# TSOC_PSoC4L.net
KiCad netlist of a schematic drawn in EAGLE
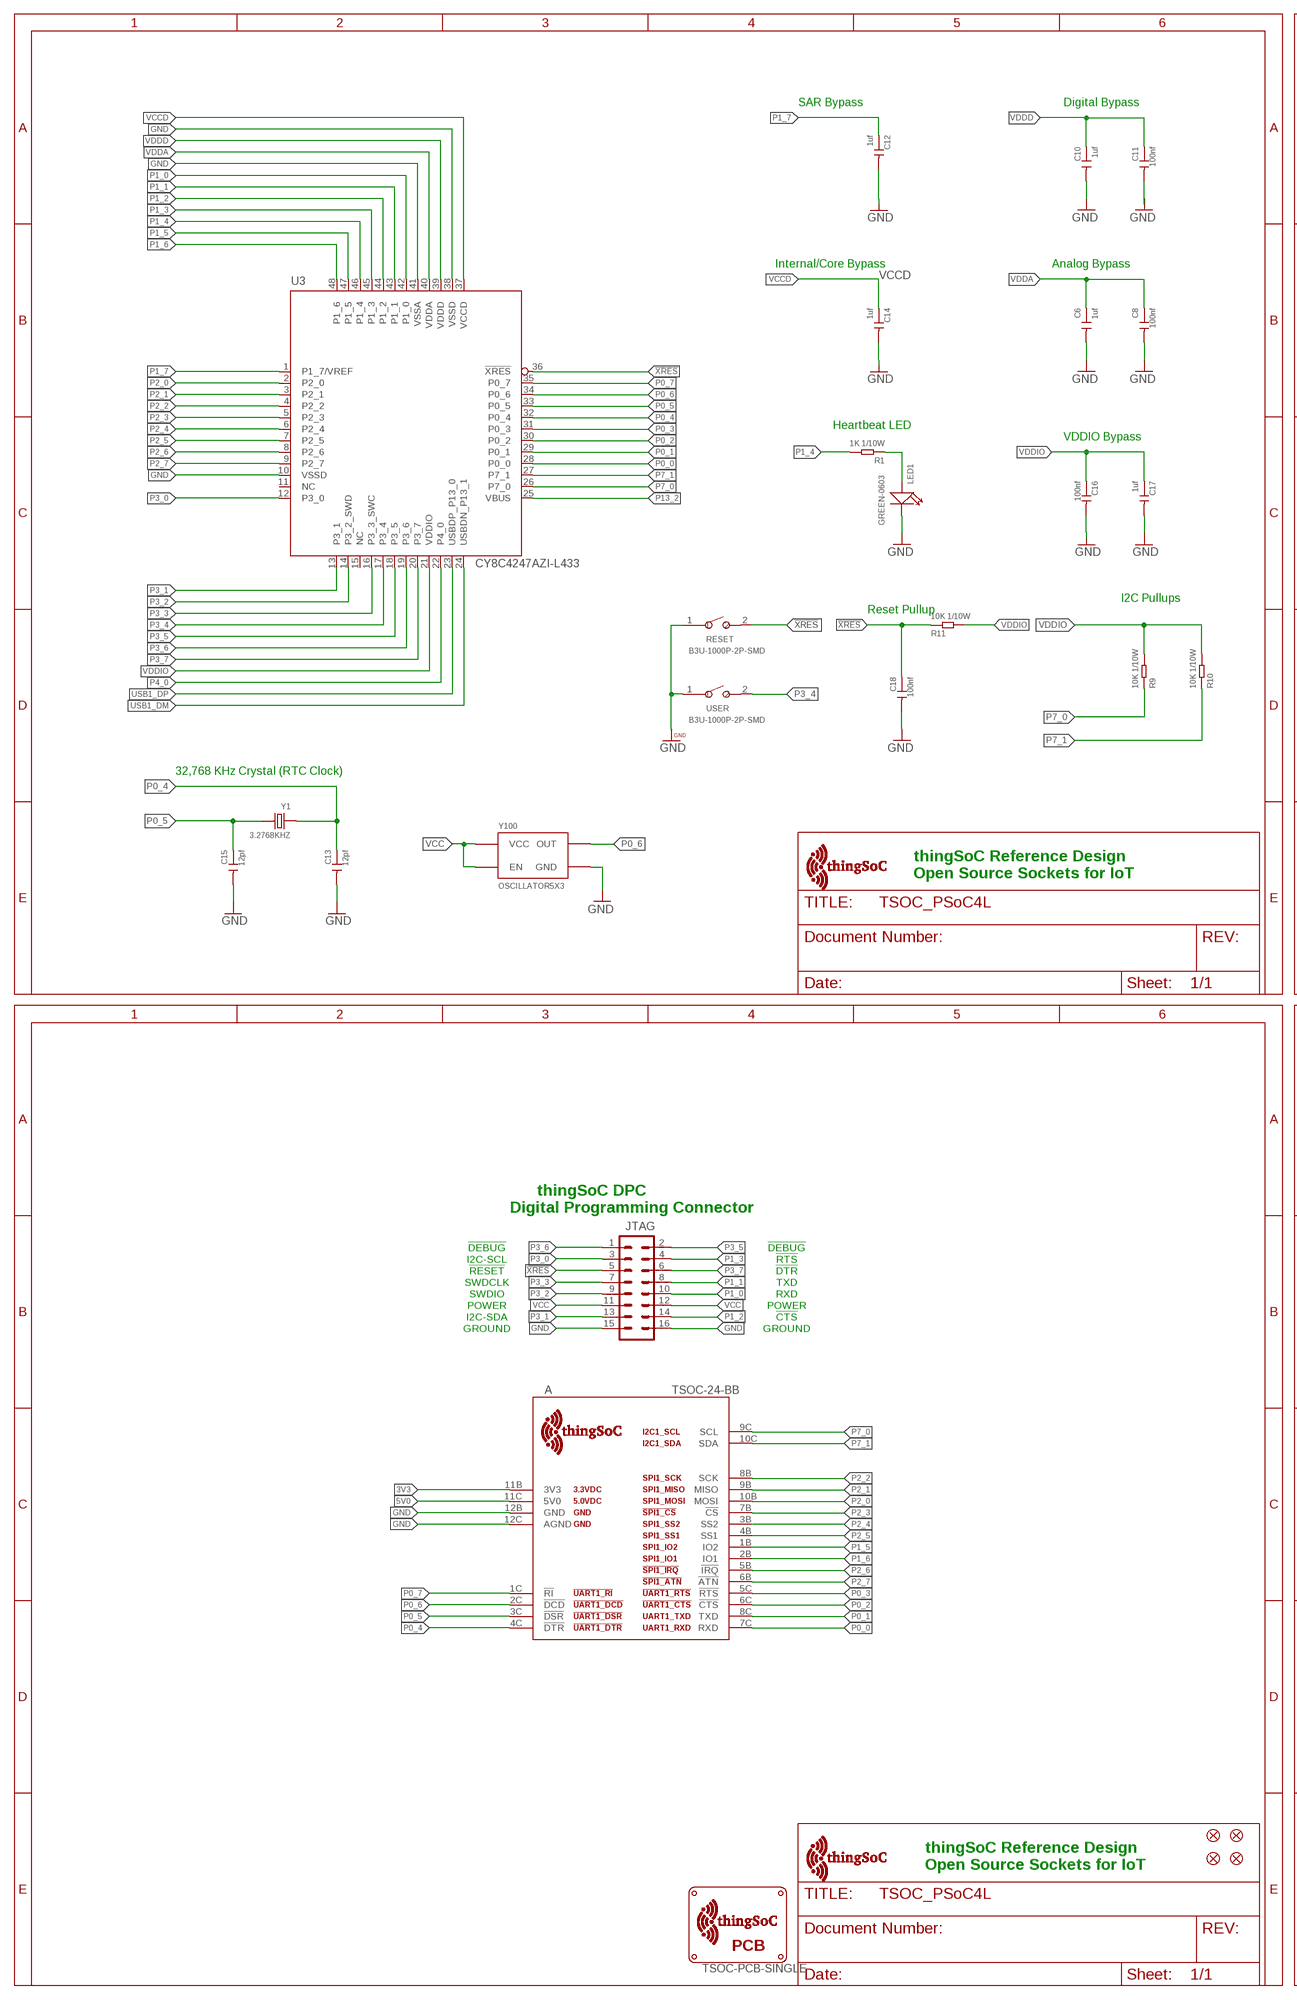
[diagram p0: schematic, sheet 1, part 1 of 2]
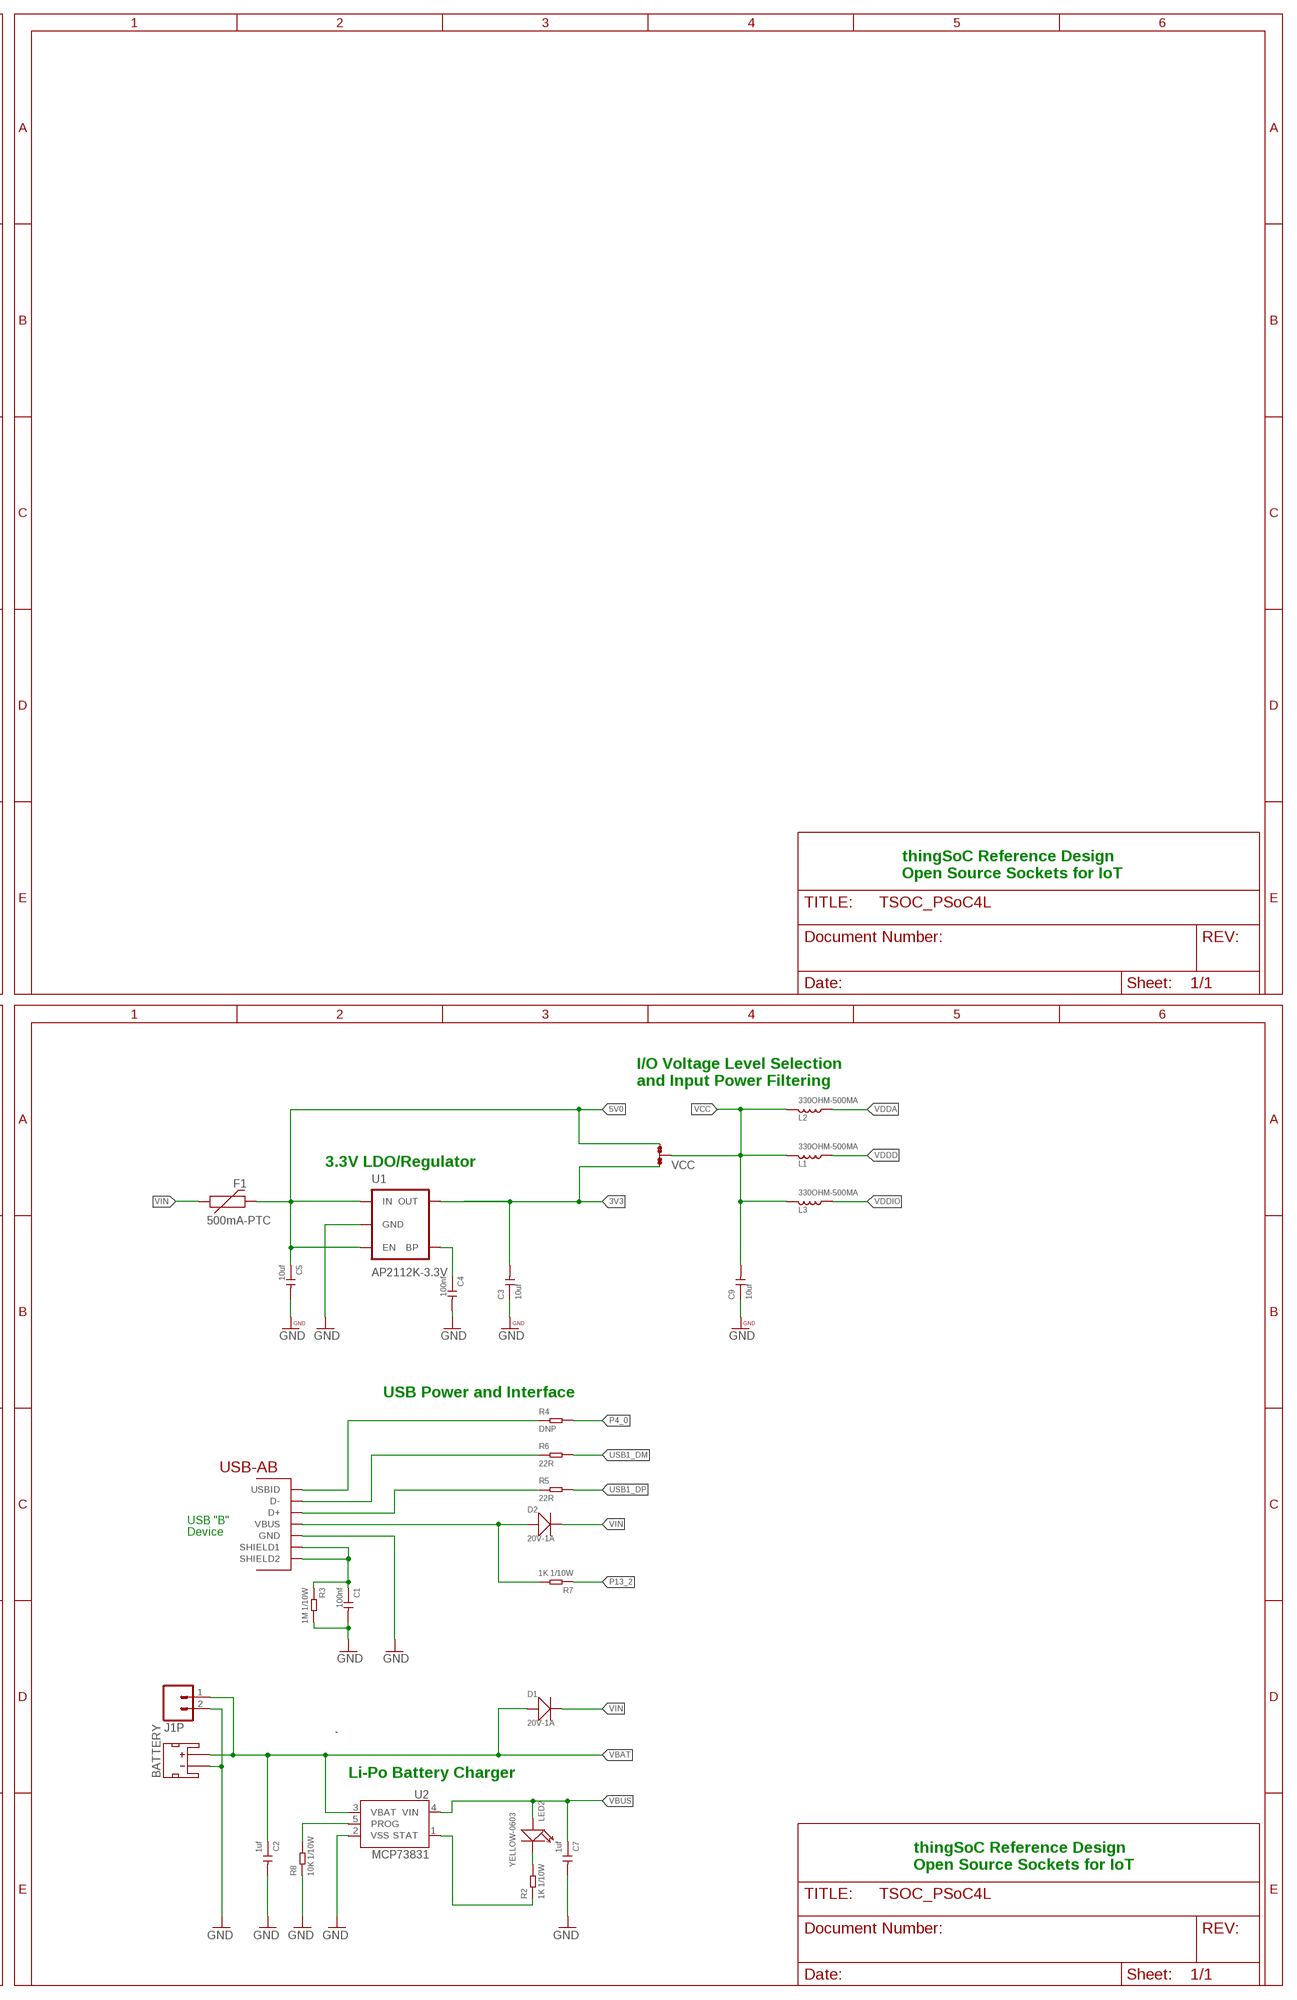
[diagram p1: schematic, sheet 1, part 2 of 2]

(export (version "E")
  (design (tool "Eeschema 10.0.6"))
  (components
    (comp (ref "A")
      (value "TSOC-24-BB")
      (footprint "eagle-import:TSOC-BB-S24")
      (libsource (lib "eagle-import") (part "TSOC-24-BB"))
    )
    (comp (ref "BATTERY")
      (value "JST_2MM_MALE")
      (footprint "eagle-import:JST-2-SMD")
      (libsource (lib "eagle-import") (part "JST_2MM_MALE"))
    )
    (comp (ref "C1")
      (value "100nf")
      (footprint "eagle-import:C0603")
      (fields (field (name "MPN") "CC0603KRX7R9BB104"))
      (libsource (lib "eagle-import") (part "CERAMIC-100NF-50V-10%-X7R(0603)"))
    )
    (comp (ref "C2")
      (value "1uf")
      (footprint "eagle-import:C0603")
      (fields (field (name "MPN") "CC0603KRX7R8BB105"))
      (libsource (lib "eagle-import") (part "CERAMIC-1UF-25V-10%-X7R(0603)"))
    )
    (comp (ref "C3")
      (value "10uf")
      (footprint "eagle-import:C0603")
      (fields (field (name "MPN") "CC0603KRX5R6BB106"))
      (libsource (lib "eagle-import") (part "CERAMIC-10UF-10V-10%-X5R(0603)"))
    )
    (comp (ref "C4")
      (value "100nf")
      (footprint "eagle-import:C0603")
      (fields (field (name "MPN") "CC0603KRX7R9BB104"))
      (libsource (lib "eagle-import") (part "CERAMIC-100NF-50V-10%-X7R(0603)"))
    )
    (comp (ref "C5")
      (value "10uf")
      (footprint "eagle-import:C0603")
      (fields (field (name "MPN") "CC0603KRX5R6BB106"))
      (libsource (lib "eagle-import") (part "CERAMIC-10UF-10V-10%-X5R(0603)"))
    )
    (comp (ref "C6")
      (value "1uf")
      (footprint "eagle-import:C0603")
      (fields (field (name "MPN") "CC0603KRX7R8BB105"))
      (libsource (lib "eagle-import") (part "CERAMIC-1UF-25V-10%-X7R(0603)"))
    )
    (comp (ref "C7")
      (value "1uf")
      (footprint "eagle-import:C0603")
      (fields (field (name "MPN") "CC0603KRX7R8BB105"))
      (libsource (lib "eagle-import") (part "CERAMIC-1UF-25V-10%-X7R(0603)"))
    )
    (comp (ref "C8")
      (value "100nf")
      (footprint "eagle-import:C0603")
      (fields (field (name "MPN") "CC0603KRX7R9BB104"))
      (libsource (lib "eagle-import") (part "CERAMIC-100NF-50V-10%-X7R(0603)"))
    )
    (comp (ref "C9")
      (value "10uf")
      (footprint "eagle-import:C0603")
      (fields (field (name "MPN") "CC0603KRX5R6BB106"))
      (libsource (lib "eagle-import") (part "CERAMIC-10UF-10V-10%-X5R(0603)"))
    )
    (comp (ref "C10")
      (value "1uf")
      (footprint "eagle-import:C0603")
      (fields (field (name "MPN") "CC0603KRX7R8BB105"))
      (libsource (lib "eagle-import") (part "CERAMIC-1UF-25V-10%-X7R(0603)"))
    )
    (comp (ref "C11")
      (value "100nf")
      (footprint "eagle-import:C0603")
      (fields (field (name "MPN") "CC0603KRX7R9BB104"))
      (libsource (lib "eagle-import") (part "CERAMIC-100NF-50V-10%-X7R(0603)"))
    )
    (comp (ref "C12")
      (value "1uf")
      (footprint "eagle-import:C0603")
      (fields (field (name "MPN") "CC0603KRX7R8BB105"))
      (libsource (lib "eagle-import") (part "CERAMIC-1UF-25V-10%-X7R(0603)"))
    )
    (comp (ref "C13")
      (value "12pf")
      (footprint "eagle-import:C0603")
      (fields (field (name "MPN") "CC0603JRNPO9BN120"))
      (libsource (lib "eagle-import") (part "CERAMIC-12PF-50V-5%-NPO(0603)"))
    )
    (comp (ref "C14")
      (value "1uf")
      (footprint "eagle-import:C0603")
      (fields (field (name "MPN") "CC0603KRX7R8BB105"))
      (libsource (lib "eagle-import") (part "CERAMIC-1UF-25V-10%-X7R(0603)"))
    )
    (comp (ref "C15")
      (value "12pf")
      (footprint "eagle-import:C0603")
      (fields (field (name "MPN") "CC0603JRNPO9BN120"))
      (libsource (lib "eagle-import") (part "CERAMIC-12PF-50V-5%-NPO(0603)"))
    )
    (comp (ref "C16")
      (value "100nf")
      (footprint "eagle-import:C0603")
      (fields (field (name "MPN") "CC0603KRX7R9BB104"))
      (libsource (lib "eagle-import") (part "CERAMIC-100NF-50V-10%-X7R(0603)"))
    )
    (comp (ref "C17")
      (value "1uf")
      (footprint "eagle-import:C0603")
      (fields (field (name "MPN") "CC0603KRX7R8BB105"))
      (libsource (lib "eagle-import") (part "CERAMIC-1UF-25V-10%-X7R(0603)"))
    )
    (comp (ref "C18")
      (value "100nf")
      (footprint "eagle-import:C0603")
      (fields (field (name "MPN") "CC0603KRX7R9BB104"))
      (libsource (lib "eagle-import") (part "CERAMIC-100NF-50V-10%-X7R(0603)"))
    )
    (comp (ref "D1")
      (value "20V-1A")
      (footprint "eagle-import:SOD-123")
      (fields (field (name "MPN") "B5819W"))
      (libsource (lib "eagle-import") (part "SMD-DIODE-SCHOTTKY-20V-1A(SOD-123)"))
    )
    (comp (ref "D2")
      (value "20V-1A")
      (footprint "eagle-import:SOD-123")
      (fields (field (name "MPN") "B5819W"))
      (libsource (lib "eagle-import") (part "SMD-DIODE-SCHOTTKY-20V-1A(SOD-123)"))
    )
    (comp (ref "F1")
      (value "500mA-PTC")
      (footprint "eagle-import:PTC-1206")
      (libsource (lib "eagle-import") (part "PTCSMD"))
    )
    (comp (ref "FID1")
      (value "FIDUCIALUFIDUCIAL")
      (footprint "eagle-import:MICRO-FIDUCIAL")
      (libsource (lib "eagle-import") (part "FIDUCIALUFIDUCIAL"))
    )
    (comp (ref "FID2")
      (value "FIDUCIALUFIDUCIAL")
      (footprint "eagle-import:MICRO-FIDUCIAL")
      (libsource (lib "eagle-import") (part "FIDUCIALUFIDUCIAL"))
    )
    (comp (ref "FID3")
      (value "FIDUCIALUFIDUCIAL")
      (footprint "eagle-import:MICRO-FIDUCIAL")
      (libsource (lib "eagle-import") (part "FIDUCIALUFIDUCIAL"))
    )
    (comp (ref "FID4")
      (value "FIDUCIALUFIDUCIAL")
      (footprint "eagle-import:MICRO-FIDUCIAL")
      (libsource (lib "eagle-import") (part "FIDUCIALUFIDUCIAL"))
    )
    (comp (ref "J1P")
      (value "M02-JST-2-PTH-NO_SILK")
      (footprint "eagle-import:JST-2-PTH-NS")
      (libsource (lib "eagle-import") (part "M02-JST-2-PTH-NO_SILK"))
    )
    (comp (ref "JTAG")
      (value "M08X2")
      (footprint "eagle-import:2X8")
      (libsource (lib "eagle-import") (part "M08X2"))
    )
    (comp (ref "L1")
      (value "330OHM-500MA")
      (footprint "eagle-import:L0603")
      (fields (field (name "MPN") "BLM18AG121SN1D"))
      (libsource (lib "eagle-import") (part "SMD-FERRITE-CHIP-120-OHM-500MA(0603)"))
    )
    (comp (ref "L2")
      (value "330OHM-500MA")
      (footprint "eagle-import:L0603")
      (fields (field (name "MPN") "BLM18AG121SN1D"))
      (libsource (lib "eagle-import") (part "SMD-FERRITE-CHIP-120-OHM-500MA(0603)"))
    )
    (comp (ref "L3")
      (value "330OHM-500MA")
      (footprint "eagle-import:L0603")
      (fields (field (name "MPN") "BLM18AG121SN1D"))
      (libsource (lib "eagle-import") (part "SMD-FERRITE-CHIP-120-OHM-500MA(0603)"))
    )
    (comp (ref "LED1")
      (value "GREEN-0603")
      (footprint "eagle-import:LED-0603")
      (fields (field (name "MPN") "19-217-G7C-AN1P2-3T"))
      (libsource (lib "eagle-import") (part "SMD-LED-CLEAR-GREEN(0603)"))
    )
    (comp (ref "LED2")
      (value "YELLOW-0603")
      (footprint "eagle-import:LED-0603")
      (fields (field (name "MPN") "19-217-Y5C-AM1N1VY-3T"))
      (libsource (lib "eagle-import") (part "SMD-LED-CLEAR-YELLOW(0603)"))
    )
    (comp (ref "R1")
      (value "1K 1/10W")
      (footprint "eagle-import:R0603")
      (fields (field (name "MPN") "RC0603JR-071KL"))
      (libsource (lib "eagle-import") (part "SMD-RES-1K-5%-1/10W(0603)"))
    )
    (comp (ref "R2")
      (value "1K 1/10W")
      (footprint "eagle-import:R0603")
      (fields (field (name "MPN") "RC0603JR-071KL"))
      (libsource (lib "eagle-import") (part "SMD-RES-1K-5%-1/10W(0603)"))
    )
    (comp (ref "R3")
      (value "1M 1/10W")
      (footprint "eagle-import:R0603")
      (fields (field (name "MPN") "RC0603JR-071ML"))
      (libsource (lib "eagle-import") (part "SMD-RES-1M-5%-1/10W(0603)"))
    )
    (comp (ref "R4")
      (value "DNP")
      (footprint "eagle-import:R0603")
      (fields (field (name "MPN") "RC0603JR-0722RL"))
      (libsource (lib "eagle-import") (part "SMD-RES-22R-5%-1/10W(0603)"))
    )
    (comp (ref "R5")
      (value "22R")
      (footprint "eagle-import:R0603")
      (fields (field (name "MPN") "RC0603JR-0722RL"))
      (libsource (lib "eagle-import") (part "SMD-RES-22R-5%-1/10W(0603)"))
    )
    (comp (ref "R6")
      (value "22R")
      (footprint "eagle-import:R0603")
      (fields (field (name "MPN") "RC0603JR-0722RL"))
      (libsource (lib "eagle-import") (part "SMD-RES-22R-5%-1/10W(0603)"))
    )
    (comp (ref "R7")
      (value "1K 1/10W")
      (footprint "eagle-import:R0603")
      (fields (field (name "MPN") "RC0603JR-071KL"))
      (libsource (lib "eagle-import") (part "SMD-RES-1K-5%-1/10W(0603)"))
    )
    (comp (ref "R8")
      (value "10K 1/10W")
      (footprint "eagle-import:R0603")
      (fields (field (name "MPN") "RC0603JR-0710KL"))
      (libsource (lib "eagle-import") (part "SMD-RES-10K-5%-1/10W(0603)"))
    )
    (comp (ref "R9")
      (value "10K 1/10W")
      (footprint "eagle-import:R0603")
      (fields (field (name "MPN") "RC0603JR-0710KL"))
      (libsource (lib "eagle-import") (part "SMD-RES-10K-5%-1/10W(0603)"))
    )
    (comp (ref "R10")
      (value "10K 1/10W")
      (footprint "eagle-import:R0603")
      (fields (field (name "MPN") "RC0603JR-0710KL"))
      (libsource (lib "eagle-import") (part "SMD-RES-10K-5%-1/10W(0603)"))
    )
    (comp (ref "R11")
      (value "10K 1/10W")
      (footprint "eagle-import:R0603")
      (fields (field (name "MPN") "RC0603JR-0710KL"))
      (libsource (lib "eagle-import") (part "SMD-RES-10K-5%-1/10W(0603)"))
    )
    (comp (ref "RESET")
      (value "B3U-1000P-2P-SMD")
      (footprint "eagle-import:SW2-2.6-3.0X2.5X1.2+0.4MM")
      (libsource (lib "eagle-import") (part "SMD-BUTTON(2P-3.0X2.5X1.2+0.4MM)-B3U-1000P-2P-SMD"))
    )
    (comp (ref "U$1")
      (value "TSOC-PCB-SINGLE")
      (footprint "eagle-import:TSOC-BB-BRD-DIM")
      (libsource (lib "eagle-import") (part "TSOC-PCB-SINGLE"))
    )
    (comp (ref "U$100")
      (value "TSOC-LOGO-LRG")
      (footprint "eagle-import:TSOC-LOGO-LRG")
      (libsource (lib "eagle-import") (part "TSOC-LOGO-LRG"))
    )
    (comp (ref "U$101")
      (value "TSOC-LOGO-SMALL")
      (footprint "eagle-import:TSOC-LOGO-SML")
      (libsource (lib "eagle-import") (part "TSOC-LOGO-SMALL"))
    )
    (comp (ref "U1")
      (value "AP2112K-3.3V")
      (footprint "eagle-import:SOT23-5")
      (libsource (lib "eagle-import") (part "V_REG_LDOSMD"))
    )
    (comp (ref "U2")
      (value "MCP73831")
      (footprint "eagle-import:SOT23-5")
      (libsource (lib "eagle-import") (part "MCP73831"))
    )
    (comp (ref "U3")
      (value "CY8C4247AZI-L433")
      (footprint "eagle-import:TQFP-7X7-48")
      (libsource (lib "eagle-import") (part "CY8C4247AZI-L433"))
    )
    (comp (ref "USB")
      (value "USB_AB")
      (footprint "eagle-import:USB-AB-MICRO-SMD")
      (libsource (lib "eagle-import") (part "USB_AB"))
    )
    (comp (ref "USER")
      (value "B3U-1000P-2P-SMD")
      (footprint "eagle-import:SW2-2.6-3.0X2.5X1.2+0.4MM")
      (libsource (lib "eagle-import") (part "SMD-BUTTON(2P-3.0X2.5X1.2+0.4MM)-B3U-1000P-2P-SMD"))
    )
    (comp (ref "VCC")
      (value "JMP-3-1_2")
      (footprint "eagle-import:JMP-3-1_2")
      (libsource (lib "eagle-import") (part "JMP-3-1_2"))
    )
    (comp (ref "Y1")
      (value "3.2768KHZ")
      (footprint "eagle-import:X2-SMD-L2.0X1.2X0.55MM")
      (fields (field (name "MPN") "FC-12M"))
      (libsource (lib "eagle-import") (part "SMD-CRYSTAL-32.768KHZ-12.5PF-20PPM-90K(2P-L2.0X1.2MM)"))
    )
    (comp (ref "Y100")
      (value "OSCILLATOR5X3")
      (footprint "eagle-import:CRYSTAL-SMD-5X3")
      (libsource (lib "eagle-import") (part "OSCILLATOR5X3"))
    )
  )
  (nets
    (net (code "1") (name "/~{XRES}") (class "Default")
      (node (ref "C18") (pin "1") (pinfunction "1_1") (pintype "passive"))
      (node (ref "JTAG") (pin "5") (pinfunction "5_5") (pintype "passive"))
      (node (ref "R11") (pin "1") (pinfunction "1_1") (pintype "passive"))
      (node (ref "RESET") (pin "2") (pinfunction "2_2") (pintype "bidirectional"))
      (node (ref "U3") (pin "36") (pinfunction "~{XRES}_36") (pintype "bidirectional"))
    )
    (net (code "2") (name "3V3") (class "Default")
      (node (ref "A") (pin "11B") (pinfunction "3V3_11B") (pintype "bidirectional"))
      (node (ref "C3") (pin "2") (pinfunction "2_2") (pintype "passive"))
      (node (ref "U1") (pin "5") (pinfunction "OUT_5") (pintype "passive"))
      (node (ref "VCC") (pin "1") (pinfunction "1_1") (pintype "passive"))
    )
    (net (code "3") (name "5V0") (class "Default")
      (node (ref "A") (pin "11C") (pinfunction "5V0_11C") (pintype "bidirectional"))
      (node (ref "C5") (pin "1") (pinfunction "1_1") (pintype "passive"))
      (node (ref "F1") (pin "2") (pinfunction "2_2") (pintype "bidirectional"))
      (node (ref "U1") (pin "1") (pinfunction "IN_1") (pintype "input"))
      (node (ref "U1") (pin "3") (pinfunction "EN_3") (pintype "input"))
      (node (ref "VCC") (pin "3") (pinfunction "3_3") (pintype "passive"))
    )
    (net (code "4") (name "GND") (class "Default")
      (node (ref "A") (pin "12B") (pinfunction "GND_12B") (pintype "bidirectional"))
      (node (ref "A") (pin "12C") (pinfunction "AGND_12C") (pintype "bidirectional"))
      (node (ref "BATTERY") (pin "1") (pinfunction "-_1") (pintype "bidirectional"))
      (node (ref "C1") (pin "2") (pinfunction "2_2") (pintype "passive"))
      (node (ref "C10") (pin "2") (pinfunction "2_2") (pintype "passive"))
      (node (ref "C11") (pin "2") (pinfunction "2_2") (pintype "passive"))
      (node (ref "C12") (pin "2") (pinfunction "2_2") (pintype "passive"))
      (node (ref "C13") (pin "2") (pinfunction "2_2") (pintype "passive"))
      (node (ref "C14") (pin "2") (pinfunction "2_2") (pintype "passive"))
      (node (ref "C15") (pin "2") (pinfunction "2_2") (pintype "passive"))
      (node (ref "C16") (pin "2") (pinfunction "2_2") (pintype "passive"))
      (node (ref "C17") (pin "2") (pinfunction "2_2") (pintype "passive"))
      (node (ref "C18") (pin "2") (pinfunction "2_2") (pintype "passive"))
      (node (ref "C2") (pin "2") (pinfunction "2_2") (pintype "passive"))
      (node (ref "C3") (pin "1") (pinfunction "1_1") (pintype "passive"))
      (node (ref "C4") (pin "2") (pinfunction "2_2") (pintype "passive"))
      (node (ref "C5") (pin "2") (pinfunction "2_2") (pintype "passive"))
      (node (ref "C6") (pin "2") (pinfunction "2_2") (pintype "passive"))
      (node (ref "C7") (pin "2") (pinfunction "2_2") (pintype "passive"))
      (node (ref "C8") (pin "2") (pinfunction "2_2") (pintype "passive"))
      (node (ref "C9") (pin "1") (pinfunction "1_1") (pintype "passive"))
      (node (ref "J1P") (pin "2") (pinfunction "2_2") (pintype "passive"))
      (node (ref "JTAG") (pin "15") (pinfunction "15_15") (pintype "passive"))
      (node (ref "JTAG") (pin "16") (pinfunction "16_16") (pintype "passive"))
      (node (ref "LED1") (pin "-") (pinfunction "-_-") (pintype "passive"))
      (node (ref "R3") (pin "2") (pinfunction "2_2") (pintype "passive"))
      (node (ref "R8") (pin "1") (pinfunction "1_1") (pintype "passive"))
      (node (ref "RESET") (pin "1") (pinfunction "1_1") (pintype "bidirectional"))
      (node (ref "U1") (pin "2") (pinfunction "GND_2") (pintype "input"))
      (node (ref "U2") (pin "2") (pinfunction "VSS_2") (pintype "power_in"))
      (node (ref "U3") (pin "10") (pinfunction "VSSD_10") (pintype "bidirectional"))
      (node (ref "U3") (pin "38") (pinfunction "VSSD_38") (pintype "bidirectional"))
      (node (ref "U3") (pin "41") (pinfunction "VSSA_41") (pintype "bidirectional"))
      (node (ref "USB") (pin "GND") (pinfunction "GND_GND") (pintype "bidirectional"))
      (node (ref "USER") (pin "1") (pinfunction "1_1") (pintype "bidirectional"))
      (node (ref "Y100") (pin "2") (pinfunction "GND_2") (pintype "bidirectional"))
    )
    (net (code "5") (name "Net-(C1-Pad1)") (class "Default")
      (node (ref "C1") (pin "1") (pinfunction "1_1") (pintype "passive"))
      (node (ref "R3") (pin "1") (pinfunction "1_1") (pintype "passive"))
      (node (ref "USB") (pin "SHIELD1") (pinfunction "SHIELD1_SHIELD1") (pintype "bidirectional"))
      (node (ref "USB") (pin "SHIELD2") (pinfunction "SHIELD2_SHIELD2") (pintype "bidirectional"))
    )
    (net (code "6") (name "Net-(LED1-Pad+)") (class "Default")
      (node (ref "LED1") (pin "+") (pinfunction "+_+") (pintype "passive"))
      (node (ref "R1") (pin "1") (pinfunction "1_1") (pintype "passive"))
    )
    (net (code "7") (name "Net-(LED2-Pad-)") (class "Default")
      (node (ref "LED2") (pin "-") (pinfunction "-_-") (pintype "passive"))
      (node (ref "R2") (pin "2") (pinfunction "2_2") (pintype "passive"))
    )
    (net (code "8") (name "Net-(R5-Pad1)") (class "Default")
      (node (ref "R5") (pin "1") (pinfunction "1_1") (pintype "passive"))
      (node (ref "USB") (pin "D+") (pinfunction "D+_D+") (pintype "bidirectional"))
    )
    (net (code "9") (name "Net-(R6-Pad1)") (class "Default")
      (node (ref "R6") (pin "1") (pinfunction "1_1") (pintype "passive"))
      (node (ref "USB") (pin "D-") (pinfunction "D-_D-") (pintype "bidirectional"))
    )
    (net (code "10") (name "Net-(U1-BP)") (class "Default")
      (node (ref "C4") (pin "1") (pinfunction "1_1") (pintype "passive"))
      (node (ref "U1") (pin "4") (pinfunction "BP_4") (pintype "input"))
    )
    (net (code "11") (name "Net-(U2-PROG)") (class "Default")
      (node (ref "R8") (pin "2") (pinfunction "2_2") (pintype "passive"))
      (node (ref "U2") (pin "5") (pinfunction "PROG_5") (pintype "input"))
    )
    (net (code "12") (name "Net-(U2-STAT)") (class "Default")
      (node (ref "R2") (pin "1") (pinfunction "1_1") (pintype "passive"))
      (node (ref "U2") (pin "1") (pinfunction "STAT_1") (pintype "output"))
    )
    (net (code "13") (name "Net-(USB-USBID)") (class "Default")
      (node (ref "R4") (pin "1") (pinfunction "1_1") (pintype "passive"))
      (node (ref "USB") (pin "ID") (pinfunction "USBID_ID") (pintype "bidirectional"))
    )
    (net (code "14") (name "P0_0") (class "Default")
      (node (ref "A") (pin "7C") (pinfunction "RXD_7C") (pintype "bidirectional"))
      (node (ref "U3") (pin "28") (pinfunction "P0_0_28") (pintype "bidirectional"))
    )
    (net (code "15") (name "P0_1") (class "Default")
      (node (ref "A") (pin "8C") (pinfunction "TXD_8C") (pintype "bidirectional"))
      (node (ref "U3") (pin "29") (pinfunction "P0_1_29") (pintype "bidirectional"))
    )
    (net (code "16") (name "P0_2") (class "Default")
      (node (ref "A") (pin "6C") (pinfunction "~{CTS}_6C") (pintype "bidirectional"))
      (node (ref "U3") (pin "30") (pinfunction "P0_2_30") (pintype "input"))
    )
    (net (code "17") (name "P0_3") (class "Default")
      (node (ref "A") (pin "5C") (pinfunction "~{RTS}_5C") (pintype "bidirectional"))
      (node (ref "U3") (pin "31") (pinfunction "P0_3_31") (pintype "bidirectional"))
    )
    (net (code "18") (name "P0_4") (class "Default")
      (node (ref "A") (pin "4C") (pinfunction "~{DTR}_4C") (pintype "bidirectional"))
      (node (ref "C13") (pin "1") (pinfunction "1_1") (pintype "passive"))
      (node (ref "U3") (pin "32") (pinfunction "P0_4_32") (pintype "bidirectional"))
      (node (ref "Y1") (pin "1") (pinfunction "1_1") (pintype "passive"))
    )
    (net (code "19") (name "P0_5") (class "Default")
      (node (ref "A") (pin "3C") (pinfunction "~{DSR}_3C") (pintype "bidirectional"))
      (node (ref "C15") (pin "1") (pinfunction "1_1") (pintype "passive"))
      (node (ref "U3") (pin "33") (pinfunction "P0_5_33") (pintype "bidirectional"))
      (node (ref "Y1") (pin "2") (pinfunction "2_2") (pintype "passive"))
    )
    (net (code "20") (name "P0_6") (class "Default")
      (node (ref "A") (pin "2C") (pinfunction "~{DCD}_2C") (pintype "bidirectional"))
      (node (ref "U3") (pin "34") (pinfunction "P0_6_34") (pintype "power_in"))
      (node (ref "Y100") (pin "3") (pinfunction "OUT_3") (pintype "bidirectional"))
    )
    (net (code "21") (name "P0_7") (class "Default")
      (node (ref "A") (pin "1C") (pinfunction "~{RI}_1C") (pintype "bidirectional"))
      (node (ref "U3") (pin "35") (pinfunction "P0_7_35") (pintype "bidirectional"))
    )
    (net (code "22") (name "P1_0") (class "Default")
      (node (ref "JTAG") (pin "10") (pinfunction "10_10") (pintype "passive"))
      (node (ref "U3") (pin "42") (pinfunction "P1_0_42") (pintype "bidirectional"))
    )
    (net (code "23") (name "P1_1") (class "Default")
      (node (ref "JTAG") (pin "8") (pinfunction "8_8") (pintype "passive"))
      (node (ref "U3") (pin "43") (pinfunction "P1_1_43") (pintype "bidirectional"))
    )
    (net (code "24") (name "P1_2") (class "Default")
      (node (ref "JTAG") (pin "14") (pinfunction "14_14") (pintype "passive"))
      (node (ref "U3") (pin "44") (pinfunction "P1_2_44") (pintype "power_in"))
    )
    (net (code "25") (name "P1_3") (class "Default")
      (node (ref "JTAG") (pin "4") (pinfunction "4_4") (pintype "passive"))
      (node (ref "U3") (pin "45") (pinfunction "P1_3_45") (pintype "bidirectional"))
    )
    (net (code "26") (name "P1_4") (class "Default")
      (node (ref "R1") (pin "2") (pinfunction "2_2") (pintype "passive"))
      (node (ref "U3") (pin "46") (pinfunction "P1_4_46") (pintype "bidirectional"))
    )
    (net (code "27") (name "P1_5") (class "Default")
      (node (ref "A") (pin "1B") (pinfunction "IO2_1B") (pintype "bidirectional"))
      (node (ref "U3") (pin "47") (pinfunction "P1_5_47") (pintype "bidirectional"))
    )
    (net (code "28") (name "P1_6") (class "Default")
      (node (ref "A") (pin "2B") (pinfunction "IO1_2B") (pintype "bidirectional"))
      (node (ref "U3") (pin "48") (pinfunction "P1_6_48") (pintype "bidirectional"))
    )
    (net (code "29") (name "P1_7") (class "Default")
      (node (ref "C12") (pin "1") (pinfunction "1_1") (pintype "passive"))
      (node (ref "U3") (pin "1") (pinfunction "P1_7/VREF_1") (pintype "bidirectional"))
    )
    (net (code "30") (name "P2_0") (class "Default")
      (node (ref "A") (pin "10B") (pinfunction "MOSI_10B") (pintype "bidirectional"))
      (node (ref "U3") (pin "2") (pinfunction "P2_0_2") (pintype "bidirectional"))
    )
    (net (code "31") (name "P2_1") (class "Default")
      (node (ref "A") (pin "9B") (pinfunction "MISO_9B") (pintype "bidirectional"))
      (node (ref "U3") (pin "3") (pinfunction "P2_1_3") (pintype "bidirectional"))
    )
    (net (code "32") (name "P2_2") (class "Default")
      (node (ref "A") (pin "8B") (pinfunction "SCK_8B") (pintype "bidirectional"))
      (node (ref "U3") (pin "4") (pinfunction "P2_2_4") (pintype "power_in"))
    )
    (net (code "33") (name "P2_3") (class "Default")
      (node (ref "A") (pin "7B") (pinfunction "~{CS}_7B") (pintype "bidirectional"))
      (node (ref "U3") (pin "5") (pinfunction "P2_3_5") (pintype "bidirectional"))
    )
    (net (code "34") (name "P2_4") (class "Default")
      (node (ref "A") (pin "3B") (pinfunction "SS2_3B") (pintype "bidirectional"))
      (node (ref "U3") (pin "6") (pinfunction "P2_4_6") (pintype "bidirectional"))
    )
    (net (code "35") (name "P2_5") (class "Default")
      (node (ref "A") (pin "4B") (pinfunction "SS1_4B") (pintype "bidirectional"))
      (node (ref "U3") (pin "7") (pinfunction "P2_5_7") (pintype "bidirectional"))
    )
    (net (code "36") (name "P2_6") (class "Default")
      (node (ref "A") (pin "5B") (pinfunction "~{IRQ}_5B") (pintype "bidirectional"))
      (node (ref "U3") (pin "8") (pinfunction "P2_6_8") (pintype "power_in"))
    )
    (net (code "37") (name "P2_7") (class "Default")
      (node (ref "A") (pin "6B") (pinfunction "~{ATN}_6B") (pintype "bidirectional"))
      (node (ref "U3") (pin "9") (pinfunction "P2_7_9") (pintype "bidirectional"))
    )
    (net (code "38") (name "P3_0") (class "Default")
      (node (ref "JTAG") (pin "3") (pinfunction "3_3") (pintype "passive"))
      (node (ref "U3") (pin "12") (pinfunction "P3_0_12") (pintype "bidirectional"))
    )
    (net (code "39") (name "P3_1") (class "Default")
      (node (ref "JTAG") (pin "13") (pinfunction "13_13") (pintype "passive"))
      (node (ref "U3") (pin "13") (pinfunction "P3_1_13") (pintype "bidirectional"))
    )
    (net (code "40") (name "P3_2") (class "Default")
      (node (ref "JTAG") (pin "9") (pinfunction "9_9") (pintype "passive"))
      (node (ref "U3") (pin "14") (pinfunction "P3_2_SWD_14") (pintype "bidirectional"))
    )
    (net (code "41") (name "P3_3") (class "Default")
      (node (ref "JTAG") (pin "7") (pinfunction "7_7") (pintype "passive"))
      (node (ref "U3") (pin "16") (pinfunction "P3_3_SWC_16") (pintype "bidirectional"))
    )
    (net (code "42") (name "P3_4") (class "Default")
      (node (ref "U3") (pin "17") (pinfunction "P3_4_17") (pintype "bidirectional"))
      (node (ref "USER") (pin "2") (pinfunction "2_2") (pintype "bidirectional"))
    )
    (net (code "43") (name "P3_5") (class "Default")
      (node (ref "JTAG") (pin "2") (pinfunction "2_2") (pintype "passive"))
      (node (ref "U3") (pin "18") (pinfunction "P3_5_18") (pintype "bidirectional"))
    )
    (net (code "44") (name "P3_6") (class "Default")
      (node (ref "JTAG") (pin "1") (pinfunction "1_1") (pintype "passive"))
      (node (ref "U3") (pin "19") (pinfunction "P3_6_19") (pintype "power_in"))
    )
    (net (code "45") (name "P3_7") (class "Default")
      (node (ref "JTAG") (pin "6") (pinfunction "6_6") (pintype "passive"))
      (node (ref "U3") (pin "20") (pinfunction "P3_7_20") (pintype "bidirectional"))
    )
    (net (code "46") (name "P4_0") (class "Default")
      (node (ref "R4") (pin "2") (pinfunction "2_2") (pintype "passive"))
      (node (ref "U3") (pin "22") (pinfunction "P4_0_22") (pintype "bidirectional"))
    )
    (net (code "47") (name "P7_0") (class "Default")
      (node (ref "A") (pin "9C") (pinfunction "SCL_9C") (pintype "bidirectional"))
      (node (ref "R9") (pin "1") (pinfunction "1_1") (pintype "passive"))
      (node (ref "U3") (pin "26") (pinfunction "P7_0_26") (pintype "bidirectional"))
    )
    (net (code "48") (name "P7_1") (class "Default")
      (node (ref "A") (pin "10C") (pinfunction "SDA_10C") (pintype "bidirectional"))
      (node (ref "R10") (pin "1") (pinfunction "1_1") (pintype "passive"))
      (node (ref "U3") (pin "27") (pinfunction "P7_1_27") (pintype "bidirectional"))
    )
    (net (code "49") (name "P13_2") (class "Default")
      (node (ref "R7") (pin "1") (pinfunction "1_1") (pintype "passive"))
      (node (ref "U3") (pin "25") (pinfunction "VBUS_25") (pintype "bidirectional"))
    )
    (net (code "50") (name "USB1_DM") (class "Default")
      (node (ref "R6") (pin "2") (pinfunction "2_2") (pintype "passive"))
      (node (ref "U3") (pin "24") (pinfunction "USBDN_P13_1_24") (pintype "bidirectional"))
    )
    (net (code "51") (name "USB1_DP") (class "Default")
      (node (ref "R5") (pin "2") (pinfunction "2_2") (pintype "passive"))
      (node (ref "U3") (pin "23") (pinfunction "USBDP_P13_0_23") (pintype "bidirectional"))
    )
    (net (code "52") (name "VBAT") (class "Default")
      (node (ref "BATTERY") (pin "2") (pinfunction "+_2") (pintype "bidirectional"))
      (node (ref "C2") (pin "1") (pinfunction "1_1") (pintype "passive"))
      (node (ref "D1") (pin "+") (pinfunction "+_+") (pintype "passive"))
      (node (ref "J1P") (pin "1") (pinfunction "1_1") (pintype "passive"))
      (node (ref "U2") (pin "3") (pinfunction "VBAT_3") (pintype "power_in"))
    )
    (net (code "53") (name "VBUS") (class "Default")
      (node (ref "C7") (pin "1") (pinfunction "1_1") (pintype "passive"))
      (node (ref "D2") (pin "+") (pinfunction "+_+") (pintype "passive"))
      (node (ref "LED2") (pin "+") (pinfunction "+_+") (pintype "passive"))
      (node (ref "R7") (pin "2") (pinfunction "2_2") (pintype "passive"))
      (node (ref "U2") (pin "4") (pinfunction "VIN_4") (pintype "power_in"))
      (node (ref "USB") (pin "VBUS") (pinfunction "VBUS_VBUS") (pintype "bidirectional"))
    )
    (net (code "54") (name "VCC") (class "Default")
      (node (ref "C9") (pin "2") (pinfunction "2_2") (pintype "passive"))
      (node (ref "JTAG") (pin "11") (pinfunction "11_11") (pintype "passive"))
      (node (ref "JTAG") (pin "12") (pinfunction "12_12") (pintype "passive"))
      (node (ref "L1") (pin "1") (pinfunction "1_1") (pintype "passive"))
      (node (ref "L2") (pin "1") (pinfunction "1_1") (pintype "passive"))
      (node (ref "L3") (pin "1") (pinfunction "1_1") (pintype "passive"))
      (node (ref "VCC") (pin "2") (pinfunction "2_2") (pintype "passive"))
      (node (ref "Y100") (pin "1") (pinfunction "EN_1") (pintype "bidirectional"))
      (node (ref "Y100") (pin "4") (pinfunction "VCC_4") (pintype "bidirectional"))
    )
    (net (code "55") (name "VCCD") (class "Default")
      (node (ref "C14") (pin "1") (pinfunction "1_1") (pintype "passive"))
      (node (ref "U3") (pin "37") (pinfunction "VCCD_37") (pintype "bidirectional"))
    )
    (net (code "56") (name "VDDA") (class "Default")
      (node (ref "C6") (pin "1") (pinfunction "1_1") (pintype "passive"))
      (node (ref "C8") (pin "1") (pinfunction "1_1") (pintype "passive"))
      (node (ref "L2") (pin "2") (pinfunction "2_2") (pintype "passive"))
      (node (ref "U3") (pin "40") (pinfunction "VDDA_40") (pintype "bidirectional"))
    )
    (net (code "57") (name "VDDD") (class "Default")
      (node (ref "C10") (pin "1") (pinfunction "1_1") (pintype "passive"))
      (node (ref "C11") (pin "1") (pinfunction "1_1") (pintype "passive"))
      (node (ref "L1") (pin "2") (pinfunction "2_2") (pintype "passive"))
      (node (ref "U3") (pin "39") (pinfunction "VDDD_39") (pintype "bidirectional"))
    )
    (net (code "58") (name "VDDIO") (class "Default")
      (node (ref "C16") (pin "1") (pinfunction "1_1") (pintype "passive"))
      (node (ref "C17") (pin "1") (pinfunction "1_1") (pintype "passive"))
      (node (ref "L3") (pin "2") (pinfunction "2_2") (pintype "passive"))
      (node (ref "R10") (pin "2") (pinfunction "2_2") (pintype "passive"))
      (node (ref "R11") (pin "2") (pinfunction "2_2") (pintype "passive"))
      (node (ref "R9") (pin "2") (pinfunction "2_2") (pintype "passive"))
      (node (ref "U3") (pin "21") (pinfunction "VDDIO_21") (pintype "bidirectional"))
    )
    (net (code "59") (name "VIN") (class "Default")
      (node (ref "D1") (pin "-") (pinfunction "-_-") (pintype "passive"))
      (node (ref "D2") (pin "-") (pinfunction "-_-") (pintype "passive"))
      (node (ref "F1") (pin "1") (pinfunction "1_1") (pintype "bidirectional"))
    )
    (net (code "60") (name "unconnected-(BATTERY-PAD1-PadNC1)") (class "Default")
      (node (ref "BATTERY") (pin "NC1") (pinfunction "PAD1_NC1") (pintype "bidirectional"))
    )
    (net (code "61") (name "unconnected-(BATTERY-PAD2-PadNC2)") (class "Default")
      (node (ref "BATTERY") (pin "NC2") (pinfunction "PAD2_NC2") (pintype "bidirectional"))
    )
    (net (code "62") (name "unconnected-(U3-NC-Pad11)") (class "Default")
      (node (ref "U3") (pin "11") (pinfunction "NC_11") (pintype "bidirectional"))
    )
    (net (code "63") (name "unconnected-(U3-NC-Pad15)") (class "Default")
      (node (ref "U3") (pin "15") (pinfunction "NC_15") (pintype "bidirectional"))
    )
  )
)
